# Dynamixel.net
KiCad netlist of a schematic drawn in Altium Designer
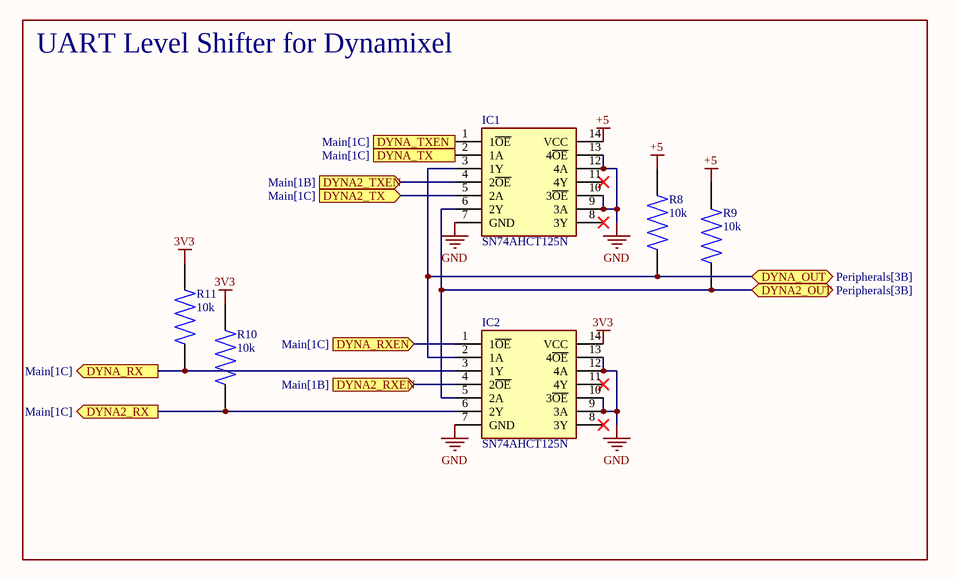
[diagram p0: Dynamixel.SchDoc]

(export (version "E")
  (design (tool "Eeschema 10.0.6"))
  (components
    (comp (ref "IC1")
      (value "SN74AHCT125N")
      (footprint "SamacSys:DIP794W53P254L1930H508Q14N")
      (description "Integrated Circuit")
      (fields (field (name "MOUSER PART NUMBER") "595-SN74AHCT125N"))
      (libsource (lib "*") (part "SN74AHCT125N"))
    )
    (comp (ref "IC2")
      (value "SN74AHCT125N")
      (footprint "SamacSys:DIP794W53P254L1930H508Q14N")
      (description "Integrated Circuit")
      (fields (field (name "MOUSER PART NUMBER") "595-SN74AHCT125N"))
      (libsource (lib "*") (part "SN74AHCT125N"))
    )
    (comp (ref "R8")
      (value "10k")
      (footprint "TNPW0805270RBETA:RESC2012X55N")
      (fields (field (name "MP") "TNPW0805270RBETA") (field (name "MF") "{'manufacturer': u'Vishay'}"))
      (libsource (lib "*") (part "TNPW0805270RBETA"))
    )
    (comp (ref "R9")
      (value "10k")
      (footprint "TNPW0805270RBETA:RESC2012X55N")
      (fields (field (name "MP") "TNPW0805270RBETA") (field (name "MF") "{'manufacturer': u'Vishay'}"))
      (libsource (lib "*") (part "TNPW0805270RBETA"))
    )
    (comp (ref "R10")
      (value "10k")
      (footprint "TNPW0805270RBETA:RESC2012X55N")
      (fields (field (name "MP") "TNPW0805270RBETA") (field (name "MF") "{'manufacturer': u'Vishay'}"))
      (libsource (lib "*") (part "TNPW0805270RBETA"))
    )
    (comp (ref "R11")
      (value "10k")
      (footprint "TNPW0805270RBETA:RESC2012X55N")
      (fields (field (name "MP") "TNPW0805270RBETA") (field (name "MF") "{'manufacturer': u'Vishay'}"))
      (libsource (lib "*") (part "TNPW0805270RBETA"))
    )
  )
  (nets
    (net (code "1") (name "+5") (class "Default")
      (node (ref "IC1") (pin "14") (pinfunction "VCC_14") (pintype "passive"))
      (node (ref "R8") (pin "2") (pinfunction "2_2") (pintype "passive"))
      (node (ref "R9") (pin "2") (pinfunction "2_2") (pintype "passive"))
    )
    (net (code "2") (name "/DYNA2_OUT") (class "Default")
      (node (ref "IC1") (pin "6") (pinfunction "2Y_6") (pintype "passive"))
      (node (ref "IC2") (pin "5") (pinfunction "2A_5") (pintype "passive"))
      (node (ref "R9") (pin "1") (pinfunction "1_1") (pintype "passive"))
    )
    (net (code "3") (name "/DYNA2_RX") (class "Default")
      (node (ref "IC2") (pin "6") (pinfunction "2Y_6") (pintype "passive"))
      (node (ref "R10") (pin "1") (pinfunction "1_1") (pintype "passive"))
    )
    (net (code "4") (name "/DYNA2_RXEN") (class "Default")
      (node (ref "IC2") (pin "4") (pinfunction "2~{OE}_4") (pintype "passive"))
    )
    (net (code "5") (name "/DYNA2_TX") (class "Default")
      (node (ref "IC1") (pin "5") (pinfunction "2A_5") (pintype "passive"))
    )
    (net (code "6") (name "/DYNA2_TXEN") (class "Default")
      (node (ref "IC1") (pin "4") (pinfunction "2~{OE}_4") (pintype "passive"))
    )
    (net (code "7") (name "/DYNA_OUT") (class "Default")
      (node (ref "IC1") (pin "3") (pinfunction "1Y_3") (pintype "passive"))
      (node (ref "IC2") (pin "2") (pinfunction "1A_2") (pintype "passive"))
      (node (ref "R8") (pin "1") (pinfunction "1_1") (pintype "passive"))
    )
    (net (code "8") (name "/DYNA_RX") (class "Default")
      (node (ref "IC2") (pin "3") (pinfunction "1Y_3") (pintype "passive"))
      (node (ref "R11") (pin "1") (pinfunction "1_1") (pintype "passive"))
    )
    (net (code "9") (name "/DYNA_RXEN") (class "Default")
      (node (ref "IC2") (pin "1") (pinfunction "1~{OE}_1") (pintype "passive"))
    )
    (net (code "10") (name "/DYNA_TX") (class "Default")
      (node (ref "IC1") (pin "2") (pinfunction "1A_2") (pintype "passive"))
    )
    (net (code "11") (name "/DYNA_TXEN") (class "Default")
      (node (ref "IC1") (pin "1") (pinfunction "1~{OE}_1") (pintype "passive"))
    )
    (net (code "12") (name "3V3") (class "Default")
      (node (ref "IC2") (pin "14") (pinfunction "VCC_14") (pintype "passive"))
      (node (ref "R10") (pin "2") (pinfunction "2_2") (pintype "passive"))
      (node (ref "R11") (pin "2") (pinfunction "2_2") (pintype "passive"))
    )
    (net (code "13") (name "GND") (class "Default")
      (node (ref "IC1") (pin "10") (pinfunction "3~{OE}_10") (pintype "passive"))
      (node (ref "IC1") (pin "12") (pinfunction "4A_12") (pintype "passive"))
      (node (ref "IC1") (pin "13") (pinfunction "4~{OE}_13") (pintype "passive"))
      (node (ref "IC1") (pin "7") (pinfunction "GND_7") (pintype "passive"))
      (node (ref "IC1") (pin "9") (pinfunction "3A_9") (pintype "passive"))
      (node (ref "IC2") (pin "10") (pinfunction "3~{OE}_10") (pintype "passive"))
      (node (ref "IC2") (pin "12") (pinfunction "4A_12") (pintype "passive"))
      (node (ref "IC2") (pin "13") (pinfunction "4~{OE}_13") (pintype "passive"))
      (node (ref "IC2") (pin "7") (pinfunction "GND_7") (pintype "passive"))
      (node (ref "IC2") (pin "9") (pinfunction "3A_9") (pintype "passive"))
    )
    (net (code "14") (name "unconnected-(IC1-3Y-Pad8)") (class "Default")
      (node (ref "IC1") (pin "8") (pinfunction "3Y_8") (pintype "passive+no_connect"))
    )
    (net (code "15") (name "unconnected-(IC1-4Y-Pad11)") (class "Default")
      (node (ref "IC1") (pin "11") (pinfunction "4Y_11") (pintype "passive+no_connect"))
    )
    (net (code "16") (name "unconnected-(IC2-3Y-Pad8)") (class "Default")
      (node (ref "IC2") (pin "8") (pinfunction "3Y_8") (pintype "passive+no_connect"))
    )
    (net (code "17") (name "unconnected-(IC2-4Y-Pad11)") (class "Default")
      (node (ref "IC2") (pin "11") (pinfunction "4Y_11") (pintype "passive+no_connect"))
    )
  )
)
